# Haptic_Sleeve_Schematic.net
KiCad netlist of a schematic drawn in EAGLE
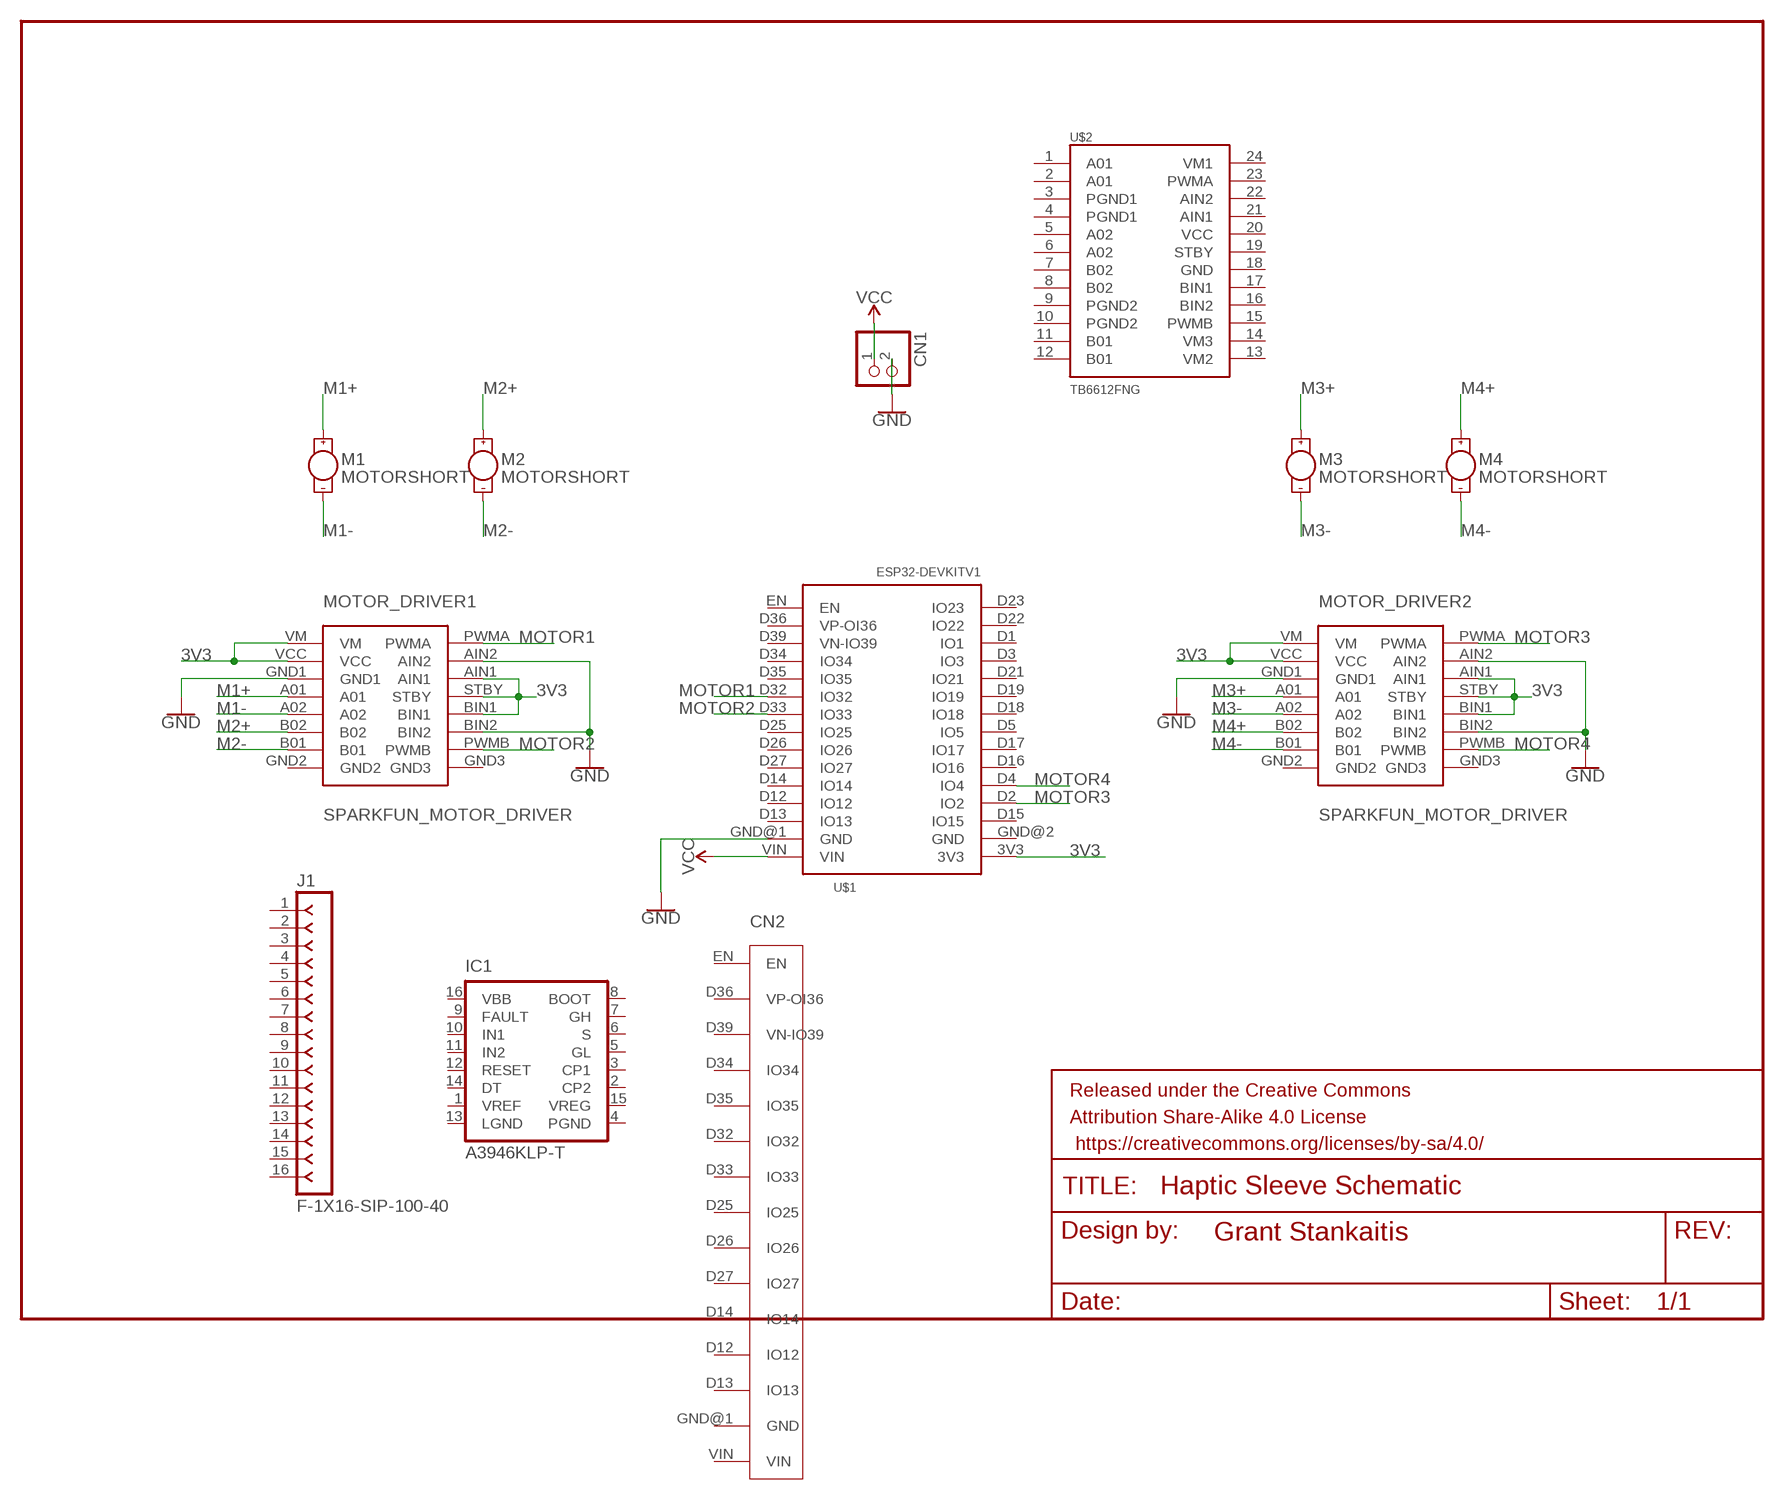
[diagram p0: schematic, sheet 1]

(export (version "E")
  (design (tool "Eeschema 10.0.6"))
  (components
    (comp (ref "CN1")
      (value "JST_2PIN-THM-RA")
      (footprint "eagle-import:JST-PH-2-THM-RA")
      (libsource (lib "eagle-import") (part "JST_2PIN-THM-RA"))
    )
    (comp (ref "CN2")
      (value "CONNECTOR1")
      (footprint "eagle-import:1X16CONNECTORPACKAGE")
      (libsource (lib "eagle-import") (part "CONNECTOR1"))
    )
    (comp (ref "FRAME1")
      (value "FRAME-LETTERNO_PACKAGE")
      (footprint "eagle-import:DUMMY")
      (fields (field (name "DESIGNER") "Grant Stankaitis") (field (name "DESIGNER_1") "Grant Stankaitis"))
      (libsource (lib "eagle-import") (part "FRAME-LETTERNO_PACKAGE"))
    )
    (comp (ref "IC1")
      (value "A3946KLP-T")
      (footprint "eagle-import:TSSOP16E")
      (libsource (lib "eagle-import") (part "A3946KLP-T"))
    )
    (comp (ref "J1")
      (value "F-1X16-SIP-100-40")
      (footprint "eagle-import:SIP-100-16-40")
      (libsource (lib "eagle-import") (part "F-1X16-SIP-100-40"))
    )
    (comp (ref "M1")
      (value "MOTORSHORT")
      (footprint "eagle-import:VIBE-MOTOR-10MM-SMD")
      (libsource (lib "eagle-import") (part "MOTORSHORT"))
    )
    (comp (ref "M2")
      (value "MOTORSHORT")
      (footprint "eagle-import:VIBE-MOTOR-10MM-SMD")
      (libsource (lib "eagle-import") (part "MOTORSHORT"))
    )
    (comp (ref "M3")
      (value "MOTORSHORT")
      (footprint "eagle-import:VIBE-MOTOR-10MM-SMD")
      (libsource (lib "eagle-import") (part "MOTORSHORT"))
    )
    (comp (ref "M4")
      (value "MOTORSHORT")
      (footprint "eagle-import:VIBE-MOTOR-10MM-SMD")
      (libsource (lib "eagle-import") (part "MOTORSHORT"))
    )
    (comp (ref "MOTOR_DRIVER1")
      (value "SPARKFUN_MOTOR_DRIVER")
      (footprint "eagle-import:SPARKFUN_MOTOR_DRIVER")
      (libsource (lib "eagle-import") (part "SPARKFUN_MOTOR_DRIVER"))
    )
    (comp (ref "MOTOR_DRIVER2")
      (value "SPARKFUN_MOTOR_DRIVER")
      (footprint "eagle-import:SPARKFUN_MOTOR_DRIVER")
      (libsource (lib "eagle-import") (part "SPARKFUN_MOTOR_DRIVER"))
    )
    (comp (ref "U$1")
      (value "ESP32DEVKITV1")
      (footprint "eagle-import:ESP32-DEVKITV1")
      (libsource (lib "eagle-import") (part "ESP32DEVKITV1"))
    )
    (comp (ref "U$2")
      (value "TB6612FNG")
      (footprint "eagle-import:SSOP24")
      (libsource (lib "eagle-import") (part "TB6612FNG"))
    )
  )
  (nets
    (net (code "1") (name "/3V3") (class "Default")
      (node (ref "MOTOR_DRIVER1") (pin "AIN1") (pinfunction "AIN1_AIN1") (pintype "bidirectional"))
      (node (ref "MOTOR_DRIVER1") (pin "BIN1") (pinfunction "BIN1_BIN1") (pintype "bidirectional"))
      (node (ref "MOTOR_DRIVER1") (pin "STBY") (pinfunction "STBY_STBY") (pintype "bidirectional"))
      (node (ref "MOTOR_DRIVER1") (pin "VCC") (pinfunction "VCC_VCC") (pintype "bidirectional"))
      (node (ref "MOTOR_DRIVER1") (pin "VM") (pinfunction "VM_VM") (pintype "bidirectional"))
      (node (ref "MOTOR_DRIVER2") (pin "AIN1") (pinfunction "AIN1_AIN1") (pintype "bidirectional"))
      (node (ref "MOTOR_DRIVER2") (pin "BIN1") (pinfunction "BIN1_BIN1") (pintype "bidirectional"))
      (node (ref "MOTOR_DRIVER2") (pin "STBY") (pinfunction "STBY_STBY") (pintype "bidirectional"))
      (node (ref "MOTOR_DRIVER2") (pin "VCC") (pinfunction "VCC_VCC") (pintype "bidirectional"))
      (node (ref "MOTOR_DRIVER2") (pin "VM") (pinfunction "VM_VM") (pintype "bidirectional"))
      (node (ref "U$1") (pin "3V3") (pinfunction "3V3_3V3") (pintype "bidirectional"))
    )
    (net (code "2") (name "/LGND") (class "Default")
      (node (ref "IC1") (pin "13") (pinfunction "LGND_13") (pintype "power_in"))
    )
    (net (code "3") (name "/M1+") (class "Default")
      (node (ref "M1") (pin "+") (pinfunction "+_+") (pintype "bidirectional"))
      (node (ref "MOTOR_DRIVER1") (pin "A01") (pinfunction "A01_A01") (pintype "bidirectional"))
    )
    (net (code "4") (name "/M1-") (class "Default")
      (node (ref "M1") (pin "-") (pinfunction "-_-") (pintype "bidirectional"))
      (node (ref "MOTOR_DRIVER1") (pin "A02") (pinfunction "A02_A02") (pintype "bidirectional"))
    )
    (net (code "5") (name "/M2+") (class "Default")
      (node (ref "M2") (pin "+") (pinfunction "+_+") (pintype "bidirectional"))
      (node (ref "MOTOR_DRIVER1") (pin "B02") (pinfunction "B02_B02") (pintype "bidirectional"))
    )
    (net (code "6") (name "/M2-") (class "Default")
      (node (ref "M2") (pin "-") (pinfunction "-_-") (pintype "bidirectional"))
      (node (ref "MOTOR_DRIVER1") (pin "B01") (pinfunction "B01_B01") (pintype "bidirectional"))
    )
    (net (code "7") (name "/M3+") (class "Default")
      (node (ref "M3") (pin "+") (pinfunction "+_+") (pintype "bidirectional"))
      (node (ref "MOTOR_DRIVER2") (pin "A01") (pinfunction "A01_A01") (pintype "bidirectional"))
    )
    (net (code "8") (name "/M3-") (class "Default")
      (node (ref "M3") (pin "-") (pinfunction "-_-") (pintype "bidirectional"))
      (node (ref "MOTOR_DRIVER2") (pin "A02") (pinfunction "A02_A02") (pintype "bidirectional"))
    )
    (net (code "9") (name "/M4+") (class "Default")
      (node (ref "M4") (pin "+") (pinfunction "+_+") (pintype "bidirectional"))
      (node (ref "MOTOR_DRIVER2") (pin "B02") (pinfunction "B02_B02") (pintype "bidirectional"))
    )
    (net (code "10") (name "/M4-") (class "Default")
      (node (ref "M4") (pin "-") (pinfunction "-_-") (pintype "bidirectional"))
      (node (ref "MOTOR_DRIVER2") (pin "B01") (pinfunction "B01_B01") (pintype "bidirectional"))
    )
    (net (code "11") (name "/MOTOR1") (class "Default")
      (node (ref "MOTOR_DRIVER1") (pin "PWMA") (pinfunction "PWMA_PWMA") (pintype "bidirectional"))
      (node (ref "U$1") (pin "D32") (pinfunction "IO32_D32") (pintype "bidirectional"))
    )
    (net (code "12") (name "/MOTOR2") (class "Default")
      (node (ref "MOTOR_DRIVER1") (pin "PWMB") (pinfunction "PWMB_PWMB") (pintype "bidirectional"))
      (node (ref "U$1") (pin "D33") (pinfunction "IO33_D33") (pintype "bidirectional"))
    )
    (net (code "13") (name "/MOTOR3") (class "Default")
      (node (ref "MOTOR_DRIVER2") (pin "PWMA") (pinfunction "PWMA_PWMA") (pintype "bidirectional"))
      (node (ref "U$1") (pin "D2") (pinfunction "IO2_D2") (pintype "bidirectional"))
    )
    (net (code "14") (name "/MOTOR4") (class "Default")
      (node (ref "MOTOR_DRIVER2") (pin "PWMB") (pinfunction "PWMB_PWMB") (pintype "bidirectional"))
      (node (ref "U$1") (pin "D4") (pinfunction "IO4_D4") (pintype "bidirectional"))
    )
    (net (code "15") (name "/PGND") (class "Default")
      (node (ref "IC1") (pin "4") (pinfunction "PGND_4") (pintype "power_in"))
    )
    (net (code "16") (name "GND") (class "Default")
      (node (ref "CN1") (pin "2") (pinfunction "1_2") (pintype "passive"))
      (node (ref "MOTOR_DRIVER1") (pin "AIN2") (pinfunction "AIN2_AIN2") (pintype "bidirectional"))
      (node (ref "MOTOR_DRIVER1") (pin "BIN2") (pinfunction "BIN2_BIN2") (pintype "bidirectional"))
      (node (ref "MOTOR_DRIVER1") (pin "GND1") (pinfunction "GND1_GND1") (pintype "bidirectional"))
      (node (ref "MOTOR_DRIVER2") (pin "AIN2") (pinfunction "AIN2_AIN2") (pintype "bidirectional"))
      (node (ref "MOTOR_DRIVER2") (pin "BIN2") (pinfunction "BIN2_BIN2") (pintype "bidirectional"))
      (node (ref "MOTOR_DRIVER2") (pin "GND1") (pinfunction "GND1_GND1") (pintype "bidirectional"))
      (node (ref "U$1") (pin "GND@1") (pinfunction "GND_GND@1") (pintype "bidirectional"))
    )
    (net (code "17") (name "VCC") (class "Default")
      (node (ref "CN1") (pin "1") (pinfunction "2_1") (pintype "passive"))
      (node (ref "U$1") (pin "VIN") (pinfunction "VIN_VIN") (pintype "bidirectional"))
    )
    (net (code "18") (name "unconnected-(CN2-GND-PadGND@1)") (class "Default")
      (node (ref "CN2") (pin "GND@1") (pinfunction "GND_GND@1") (pintype "bidirectional"))
    )
    (net (code "19") (name "unconnected-(CN2-IO12-PadD12)") (class "Default")
      (node (ref "CN2") (pin "D12") (pinfunction "IO12_D12") (pintype "bidirectional"))
    )
    (net (code "20") (name "unconnected-(CN2-IO13-PadD13)") (class "Default")
      (node (ref "CN2") (pin "D13") (pinfunction "IO13_D13") (pintype "bidirectional"))
    )
    (net (code "21") (name "unconnected-(CN2-IO14-PadD14)") (class "Default")
      (node (ref "CN2") (pin "D14") (pinfunction "IO14_D14") (pintype "bidirectional"))
    )
    (net (code "22") (name "unconnected-(CN2-IO25-PadD25)") (class "Default")
      (node (ref "CN2") (pin "D25") (pinfunction "IO25_D25") (pintype "bidirectional"))
    )
    (net (code "23") (name "unconnected-(CN2-IO26-PadD26)") (class "Default")
      (node (ref "CN2") (pin "D26") (pinfunction "IO26_D26") (pintype "bidirectional"))
    )
    (net (code "24") (name "unconnected-(CN2-IO27-PadD27)") (class "Default")
      (node (ref "CN2") (pin "D27") (pinfunction "IO27_D27") (pintype "bidirectional"))
    )
    (net (code "25") (name "unconnected-(CN2-IO32-PadD32)") (class "Default")
      (node (ref "CN2") (pin "D32") (pinfunction "IO32_D32") (pintype "bidirectional"))
    )
    (net (code "26") (name "unconnected-(CN2-IO33-PadD33)") (class "Default")
      (node (ref "CN2") (pin "D33") (pinfunction "IO33_D33") (pintype "bidirectional"))
    )
    (net (code "27") (name "unconnected-(CN2-IO34-PadD34)") (class "Default")
      (node (ref "CN2") (pin "D34") (pinfunction "IO34_D34") (pintype "bidirectional"))
    )
    (net (code "28") (name "unconnected-(CN2-IO35-PadD35)") (class "Default")
      (node (ref "CN2") (pin "D35") (pinfunction "IO35_D35") (pintype "bidirectional"))
    )
    (net (code "29") (name "unconnected-(CN2-PadEN)") (class "Default")
      (node (ref "CN2") (pin "EN") (pinfunction "EN_EN") (pintype "bidirectional"))
    )
    (net (code "30") (name "unconnected-(CN2-PadVIN)") (class "Default")
      (node (ref "CN2") (pin "VIN") (pinfunction "VIN_VIN") (pintype "bidirectional"))
    )
    (net (code "31") (name "unconnected-(CN2-VN-IO39-PadD39)") (class "Default")
      (node (ref "CN2") (pin "D39") (pinfunction "VN-IO39_D39") (pintype "bidirectional"))
    )
    (net (code "32") (name "unconnected-(CN2-VP-OI36-PadD36)") (class "Default")
      (node (ref "CN2") (pin "D36") (pinfunction "VP-OI36_D36") (pintype "bidirectional"))
    )
    (net (code "33") (name "unconnected-(IC1-BOOT-Pad8)") (class "Default")
      (node (ref "IC1") (pin "8") (pinfunction "BOOT_8") (pintype "input"))
    )
    (net (code "34") (name "unconnected-(IC1-CP1-Pad3)") (class "Default")
      (node (ref "IC1") (pin "3") (pinfunction "CP1_3") (pintype "passive"))
    )
    (net (code "35") (name "unconnected-(IC1-CP2-Pad2)") (class "Default")
      (node (ref "IC1") (pin "2") (pinfunction "CP2_2") (pintype "passive"))
    )
    (net (code "36") (name "unconnected-(IC1-DT-Pad14)") (class "Default")
      (node (ref "IC1") (pin "14") (pinfunction "DT_14") (pintype "passive"))
    )
    (net (code "37") (name "unconnected-(IC1-FAULT-Pad9)") (class "Default")
      (node (ref "IC1") (pin "9") (pinfunction "FAULT_9") (pintype "output"))
    )
    (net (code "38") (name "unconnected-(IC1-GH-Pad7)") (class "Default")
      (node (ref "IC1") (pin "7") (pinfunction "GH_7") (pintype "output"))
    )
    (net (code "39") (name "unconnected-(IC1-GL-Pad5)") (class "Default")
      (node (ref "IC1") (pin "5") (pinfunction "GL_5") (pintype "output"))
    )
    (net (code "40") (name "unconnected-(IC1-IN1-Pad10)") (class "Default")
      (node (ref "IC1") (pin "10") (pinfunction "IN1_10") (pintype "input"))
    )
    (net (code "41") (name "unconnected-(IC1-IN2-Pad11)") (class "Default")
      (node (ref "IC1") (pin "11") (pinfunction "IN2_11") (pintype "input"))
    )
    (net (code "42") (name "unconnected-(IC1-RESET-Pad12)") (class "Default")
      (node (ref "IC1") (pin "12") (pinfunction "RESET_12") (pintype "input"))
    )
    (net (code "43") (name "unconnected-(IC1-S-Pad6)") (class "Default")
      (node (ref "IC1") (pin "6") (pinfunction "S_6") (pintype "input"))
    )
    (net (code "44") (name "unconnected-(IC1-VBB-Pad16)") (class "Default")
      (node (ref "IC1") (pin "16") (pinfunction "VBB_16") (pintype "input"))
    )
    (net (code "45") (name "unconnected-(IC1-VREF-Pad1)") (class "Default")
      (node (ref "IC1") (pin "1") (pinfunction "VREF_1") (pintype "passive"))
    )
    (net (code "46") (name "unconnected-(IC1-VREG-Pad15)") (class "Default")
      (node (ref "IC1") (pin "15") (pinfunction "VREG_15") (pintype "passive"))
    )
    (net (code "47") (name "unconnected-(J1-Pad1)") (class "Default")
      (node (ref "J1") (pin "1") (pinfunction "1_1") (pintype "passive"))
    )
    (net (code "48") (name "unconnected-(J1-Pad2)") (class "Default")
      (node (ref "J1") (pin "2") (pinfunction "2_2") (pintype "passive"))
    )
    (net (code "49") (name "unconnected-(J1-Pad3)") (class "Default")
      (node (ref "J1") (pin "3") (pinfunction "3_3") (pintype "passive"))
    )
    (net (code "50") (name "unconnected-(J1-Pad4)") (class "Default")
      (node (ref "J1") (pin "4") (pinfunction "4_4") (pintype "passive"))
    )
    (net (code "51") (name "unconnected-(J1-Pad5)") (class "Default")
      (node (ref "J1") (pin "5") (pinfunction "5_5") (pintype "passive"))
    )
    (net (code "52") (name "unconnected-(J1-Pad6)") (class "Default")
      (node (ref "J1") (pin "6") (pinfunction "6_6") (pintype "passive"))
    )
    (net (code "53") (name "unconnected-(J1-Pad7)") (class "Default")
      (node (ref "J1") (pin "7") (pinfunction "7_7") (pintype "passive"))
    )
    (net (code "54") (name "unconnected-(J1-Pad8)") (class "Default")
      (node (ref "J1") (pin "8") (pinfunction "8_8") (pintype "passive"))
    )
    (net (code "55") (name "unconnected-(J1-Pad9)") (class "Default")
      (node (ref "J1") (pin "9") (pinfunction "9_9") (pintype "passive"))
    )
    (net (code "56") (name "unconnected-(J1-Pad10)") (class "Default")
      (node (ref "J1") (pin "10") (pinfunction "10_10") (pintype "passive"))
    )
    (net (code "57") (name "unconnected-(J1-Pad11)") (class "Default")
      (node (ref "J1") (pin "11") (pinfunction "11_11") (pintype "passive"))
    )
    (net (code "58") (name "unconnected-(J1-Pad12)") (class "Default")
      (node (ref "J1") (pin "12") (pinfunction "12_12") (pintype "passive"))
    )
    (net (code "59") (name "unconnected-(J1-Pad13)") (class "Default")
      (node (ref "J1") (pin "13") (pinfunction "13_13") (pintype "passive"))
    )
    (net (code "60") (name "unconnected-(J1-Pad14)") (class "Default")
      (node (ref "J1") (pin "14") (pinfunction "14_14") (pintype "passive"))
    )
    (net (code "61") (name "unconnected-(J1-Pad15)") (class "Default")
      (node (ref "J1") (pin "15") (pinfunction "15_15") (pintype "passive"))
    )
    (net (code "62") (name "unconnected-(J1-Pad16)") (class "Default")
      (node (ref "J1") (pin "16") (pinfunction "16_16") (pintype "passive"))
    )
    (net (code "63") (name "unconnected-(MOTOR_DRIVER1-PadGND2)") (class "Default")
      (node (ref "MOTOR_DRIVER1") (pin "GND2") (pinfunction "GND2_GND2") (pintype "bidirectional"))
    )
    (net (code "64") (name "unconnected-(MOTOR_DRIVER1-PadGND3)") (class "Default")
      (node (ref "MOTOR_DRIVER1") (pin "GND3") (pinfunction "GND3_GND3") (pintype "bidirectional"))
    )
    (net (code "65") (name "unconnected-(MOTOR_DRIVER2-PadGND2)") (class "Default")
      (node (ref "MOTOR_DRIVER2") (pin "GND2") (pinfunction "GND2_GND2") (pintype "bidirectional"))
    )
    (net (code "66") (name "unconnected-(MOTOR_DRIVER2-PadGND3)") (class "Default")
      (node (ref "MOTOR_DRIVER2") (pin "GND3") (pinfunction "GND3_GND3") (pintype "bidirectional"))
    )
    (net (code "67") (name "unconnected-(U$1-GND-PadGND@2)") (class "Default")
      (node (ref "U$1") (pin "GND@2") (pinfunction "GND_GND@2") (pintype "bidirectional"))
    )
    (net (code "68") (name "unconnected-(U$1-IO1-PadD1)") (class "Default")
      (node (ref "U$1") (pin "D1") (pinfunction "IO1_D1") (pintype "bidirectional"))
    )
    (net (code "69") (name "unconnected-(U$1-IO3-PadD3)") (class "Default")
      (node (ref "U$1") (pin "D3") (pinfunction "IO3_D3") (pintype "bidirectional"))
    )
    (net (code "70") (name "unconnected-(U$1-IO5-PadD5)") (class "Default")
      (node (ref "U$1") (pin "D5") (pinfunction "IO5_D5") (pintype "bidirectional"))
    )
    (net (code "71") (name "unconnected-(U$1-IO12-PadD12)") (class "Default")
      (node (ref "U$1") (pin "D12") (pinfunction "IO12_D12") (pintype "bidirectional"))
    )
    (net (code "72") (name "unconnected-(U$1-IO13-PadD13)") (class "Default")
      (node (ref "U$1") (pin "D13") (pinfunction "IO13_D13") (pintype "bidirectional"))
    )
    (net (code "73") (name "unconnected-(U$1-IO14-PadD14)") (class "Default")
      (node (ref "U$1") (pin "D14") (pinfunction "IO14_D14") (pintype "bidirectional"))
    )
    (net (code "74") (name "unconnected-(U$1-IO15-PadD15)") (class "Default")
      (node (ref "U$1") (pin "D15") (pinfunction "IO15_D15") (pintype "bidirectional"))
    )
    (net (code "75") (name "unconnected-(U$1-IO16-PadD16)") (class "Default")
      (node (ref "U$1") (pin "D16") (pinfunction "IO16_D16") (pintype "bidirectional"))
    )
    (net (code "76") (name "unconnected-(U$1-IO17-PadD17)") (class "Default")
      (node (ref "U$1") (pin "D17") (pinfunction "IO17_D17") (pintype "bidirectional"))
    )
    (net (code "77") (name "unconnected-(U$1-IO18-PadD18)") (class "Default")
      (node (ref "U$1") (pin "D18") (pinfunction "IO18_D18") (pintype "bidirectional"))
    )
    (net (code "78") (name "unconnected-(U$1-IO19-PadD19)") (class "Default")
      (node (ref "U$1") (pin "D19") (pinfunction "IO19_D19") (pintype "bidirectional"))
    )
    (net (code "79") (name "unconnected-(U$1-IO21-PadD21)") (class "Default")
      (node (ref "U$1") (pin "D21") (pinfunction "IO21_D21") (pintype "bidirectional"))
    )
    (net (code "80") (name "unconnected-(U$1-IO22-PadD22)") (class "Default")
      (node (ref "U$1") (pin "D22") (pinfunction "IO22_D22") (pintype "bidirectional"))
    )
    (net (code "81") (name "unconnected-(U$1-IO23-PadD23)") (class "Default")
      (node (ref "U$1") (pin "D23") (pinfunction "IO23_D23") (pintype "bidirectional"))
    )
    (net (code "82") (name "unconnected-(U$1-IO25-PadD25)") (class "Default")
      (node (ref "U$1") (pin "D25") (pinfunction "IO25_D25") (pintype "bidirectional"))
    )
    (net (code "83") (name "unconnected-(U$1-IO26-PadD26)") (class "Default")
      (node (ref "U$1") (pin "D26") (pinfunction "IO26_D26") (pintype "bidirectional"))
    )
    (net (code "84") (name "unconnected-(U$1-IO27-PadD27)") (class "Default")
      (node (ref "U$1") (pin "D27") (pinfunction "IO27_D27") (pintype "bidirectional"))
    )
    (net (code "85") (name "unconnected-(U$1-IO34-PadD34)") (class "Default")
      (node (ref "U$1") (pin "D34") (pinfunction "IO34_D34") (pintype "bidirectional"))
    )
    (net (code "86") (name "unconnected-(U$1-IO35-PadD35)") (class "Default")
      (node (ref "U$1") (pin "D35") (pinfunction "IO35_D35") (pintype "bidirectional"))
    )
    (net (code "87") (name "unconnected-(U$1-PadEN)") (class "Default")
      (node (ref "U$1") (pin "EN") (pinfunction "EN_EN") (pintype "bidirectional"))
    )
    (net (code "88") (name "unconnected-(U$1-VN-IO39-PadD39)") (class "Default")
      (node (ref "U$1") (pin "D39") (pinfunction "VN-IO39_D39") (pintype "bidirectional"))
    )
    (net (code "89") (name "unconnected-(U$1-VP-OI36-PadD36)") (class "Default")
      (node (ref "U$1") (pin "D36") (pinfunction "VP-OI36_D36") (pintype "bidirectional"))
    )
    (net (code "90") (name "unconnected-(U$2-A01-Pad1)") (class "Default")
      (node (ref "U$2") (pin "1") (pinfunction "A01_1") (pintype "bidirectional"))
    )
    (net (code "91") (name "unconnected-(U$2-A01-Pad2)") (class "Default")
      (node (ref "U$2") (pin "2") (pinfunction "A01_2") (pintype "bidirectional"))
    )
    (net (code "92") (name "unconnected-(U$2-A02-Pad5)") (class "Default")
      (node (ref "U$2") (pin "5") (pinfunction "A02_5") (pintype "bidirectional"))
    )
    (net (code "93") (name "unconnected-(U$2-A02-Pad6)") (class "Default")
      (node (ref "U$2") (pin "6") (pinfunction "A02_6") (pintype "bidirectional"))
    )
    (net (code "94") (name "unconnected-(U$2-AIN1-Pad21)") (class "Default")
      (node (ref "U$2") (pin "21") (pinfunction "AIN1_21") (pintype "bidirectional"))
    )
    (net (code "95") (name "unconnected-(U$2-AIN2-Pad22)") (class "Default")
      (node (ref "U$2") (pin "22") (pinfunction "AIN2_22") (pintype "bidirectional"))
    )
    (net (code "96") (name "unconnected-(U$2-B01-Pad11)") (class "Default")
      (node (ref "U$2") (pin "11") (pinfunction "B01_11") (pintype "bidirectional"))
    )
    (net (code "97") (name "unconnected-(U$2-B01-Pad12)") (class "Default")
      (node (ref "U$2") (pin "12") (pinfunction "B01_12") (pintype "bidirectional"))
    )
    (net (code "98") (name "unconnected-(U$2-B02-Pad7)") (class "Default")
      (node (ref "U$2") (pin "7") (pinfunction "B02_7") (pintype "bidirectional"))
    )
    (net (code "99") (name "unconnected-(U$2-B02-Pad8)") (class "Default")
      (node (ref "U$2") (pin "8") (pinfunction "B02_8") (pintype "bidirectional"))
    )
    (net (code "100") (name "unconnected-(U$2-BIN1-Pad17)") (class "Default")
      (node (ref "U$2") (pin "17") (pinfunction "BIN1_17") (pintype "bidirectional"))
    )
    (net (code "101") (name "unconnected-(U$2-BIN2-Pad16)") (class "Default")
      (node (ref "U$2") (pin "16") (pinfunction "BIN2_16") (pintype "bidirectional"))
    )
    (net (code "102") (name "unconnected-(U$2-GND-Pad18)") (class "Default")
      (node (ref "U$2") (pin "18") (pinfunction "GND_18") (pintype "bidirectional"))
    )
    (net (code "103") (name "unconnected-(U$2-PGND1-Pad3)") (class "Default")
      (node (ref "U$2") (pin "3") (pinfunction "PGND1_3") (pintype "bidirectional"))
    )
    (net (code "104") (name "unconnected-(U$2-PGND1-Pad4)") (class "Default")
      (node (ref "U$2") (pin "4") (pinfunction "PGND1_4") (pintype "bidirectional"))
    )
    (net (code "105") (name "unconnected-(U$2-PGND2-Pad9)") (class "Default")
      (node (ref "U$2") (pin "9") (pinfunction "PGND2_9") (pintype "bidirectional"))
    )
    (net (code "106") (name "unconnected-(U$2-PGND2-Pad10)") (class "Default")
      (node (ref "U$2") (pin "10") (pinfunction "PGND2_10") (pintype "bidirectional"))
    )
    (net (code "107") (name "unconnected-(U$2-PWMA-Pad23)") (class "Default")
      (node (ref "U$2") (pin "23") (pinfunction "PWMA_23") (pintype "bidirectional"))
    )
    (net (code "108") (name "unconnected-(U$2-PWMB-Pad15)") (class "Default")
      (node (ref "U$2") (pin "15") (pinfunction "PWMB_15") (pintype "bidirectional"))
    )
    (net (code "109") (name "unconnected-(U$2-STBY-Pad19)") (class "Default")
      (node (ref "U$2") (pin "19") (pinfunction "STBY_19") (pintype "bidirectional"))
    )
    (net (code "110") (name "unconnected-(U$2-VCC-Pad20)") (class "Default")
      (node (ref "U$2") (pin "20") (pinfunction "VCC_20") (pintype "bidirectional"))
    )
    (net (code "111") (name "unconnected-(U$2-VM1-Pad24)") (class "Default")
      (node (ref "U$2") (pin "24") (pinfunction "VM1_24") (pintype "bidirectional"))
    )
    (net (code "112") (name "unconnected-(U$2-VM2-Pad13)") (class "Default")
      (node (ref "U$2") (pin "13") (pinfunction "VM2_13") (pintype "bidirectional"))
    )
    (net (code "113") (name "unconnected-(U$2-VM3-Pad14)") (class "Default")
      (node (ref "U$2") (pin "14") (pinfunction "VM3_14") (pintype "bidirectional"))
    )
  )
)
